# power.net
KiCad netlist of a schematic drawn in Altium Designer
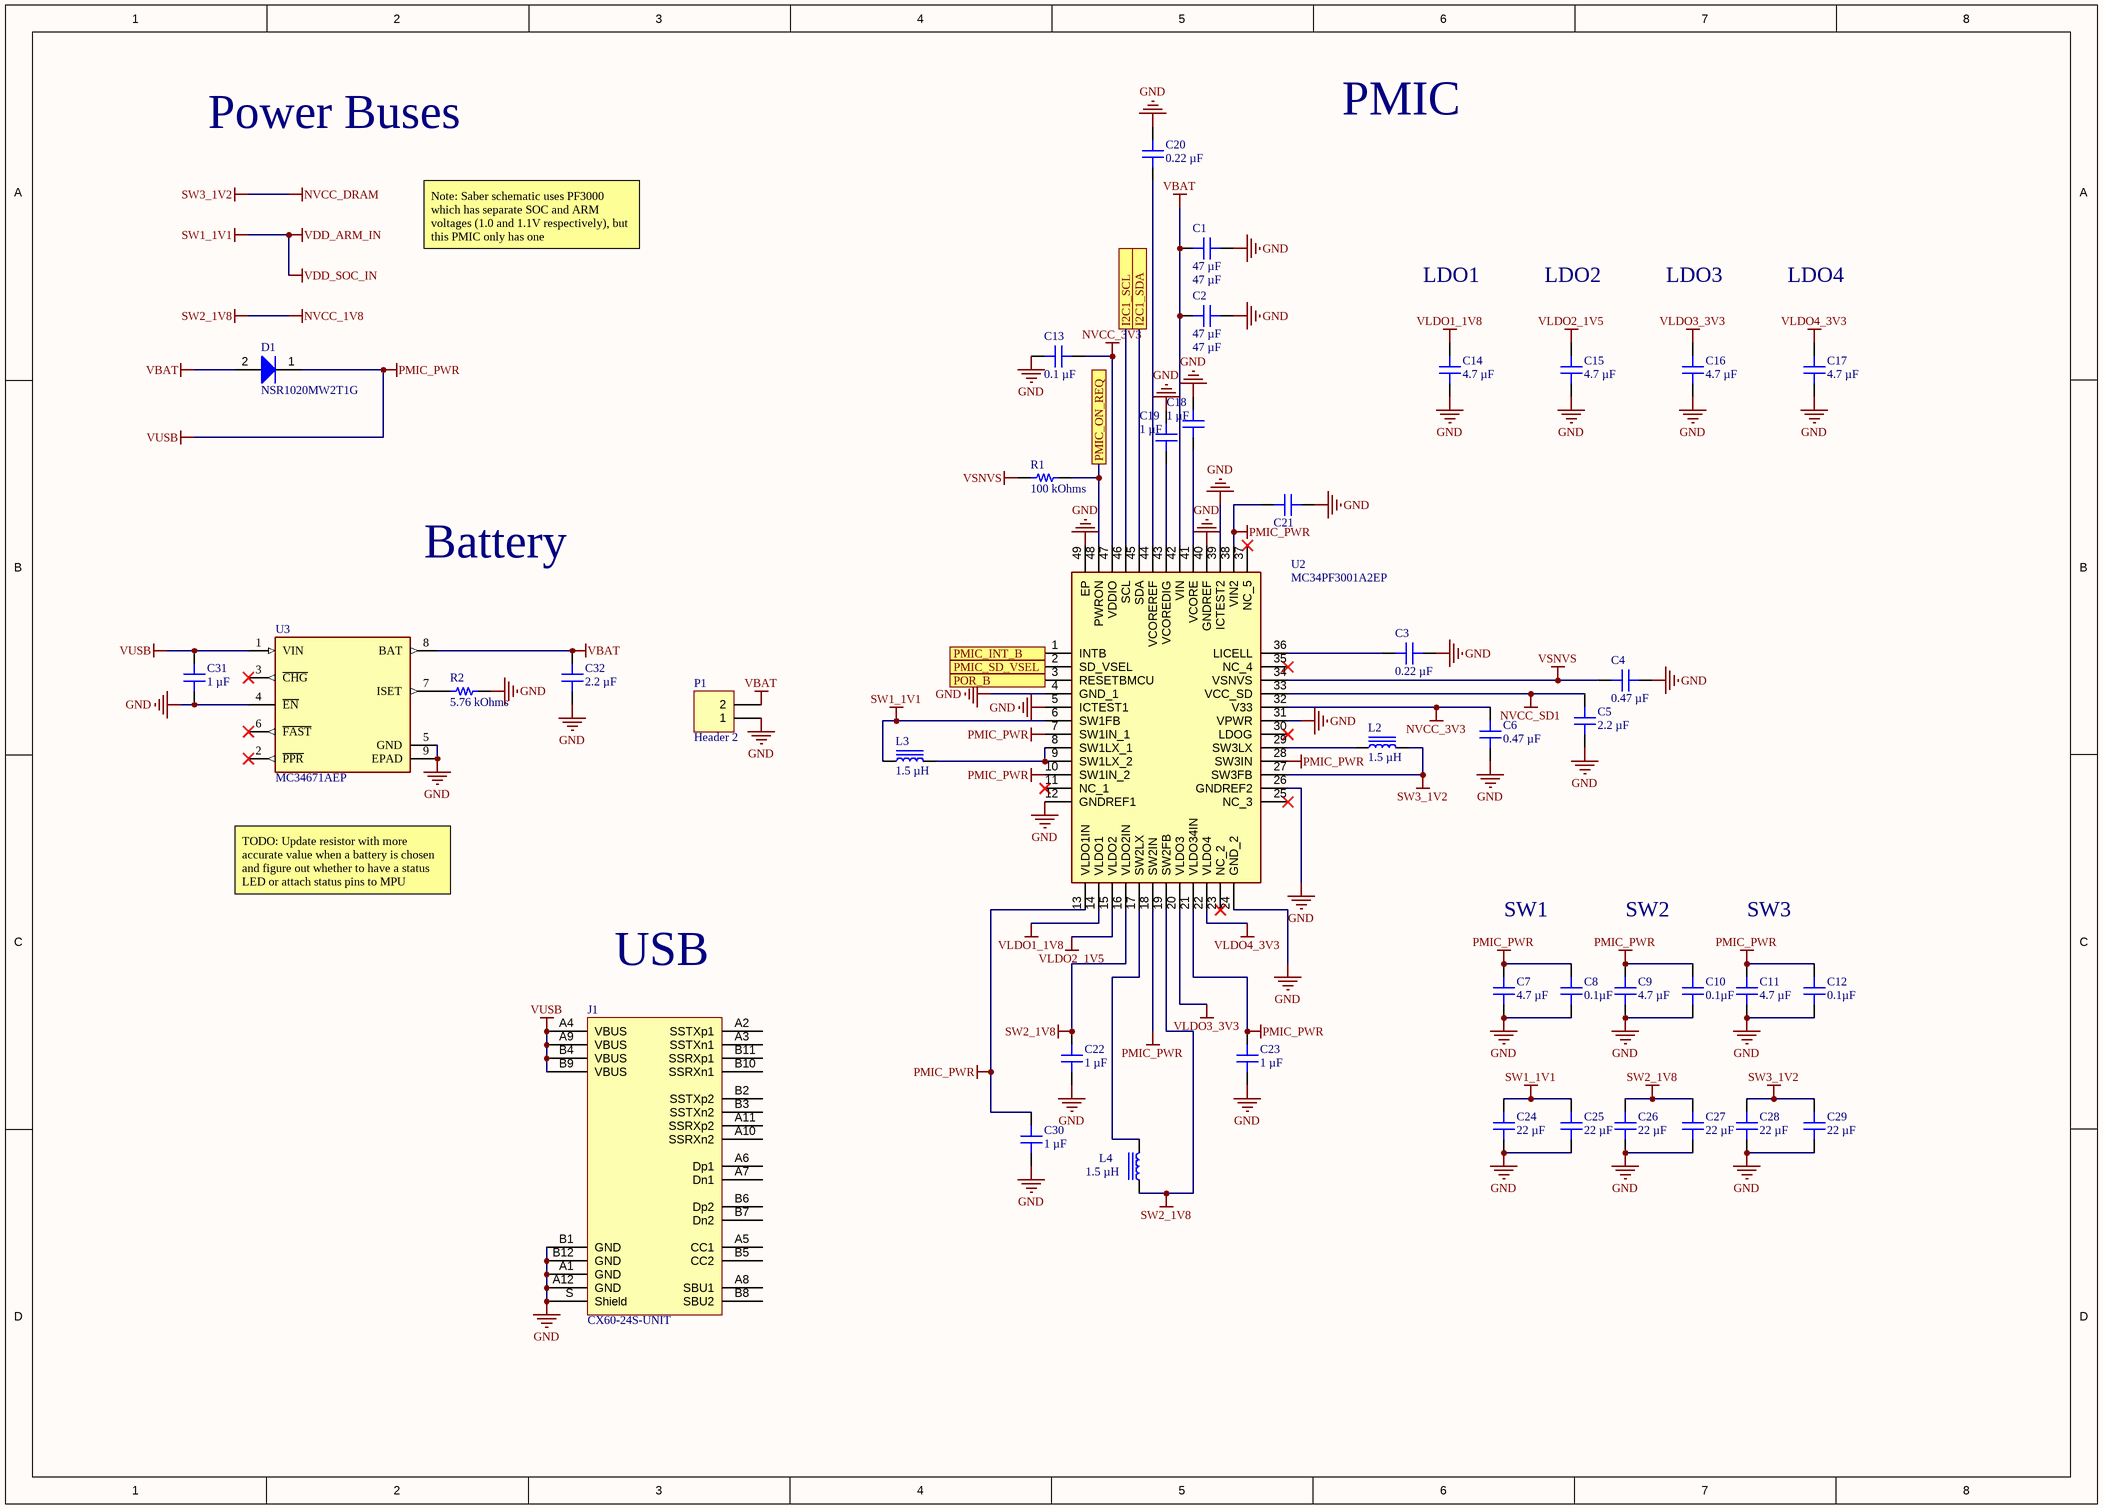
[diagram p0: power.SchDoc]

(export (version "E")
  (design (tool "Eeschema 10.0.6"))
  (components
    (comp (ref "C1")
      (value "47 µF")
      (footprint "CAP 0603_1608")
      (description "CAP CER 47UF 4V X5R 0603")
      (fields (field (name "PART NUMBER") "GRM188R60G476ME15D") (field (name "ALTIUM_VALUE") "47 µF"))
      (libsource (lib "Celestial Altium Library - altium_library") (part "Capacitor"))
    )
    (comp (ref "C2")
      (value "47 µF")
      (footprint "CAP 0603_1608")
      (description "CAP CER 47UF 4V X5R 0603")
      (fields (field (name "PART NUMBER") "GRM188R60G476ME15D") (field (name "ALTIUM_VALUE") "47 µF"))
      (libsource (lib "Celestial Altium Library - altium_library") (part "Capacitor"))
    )
    (comp (ref "C3")
      (value "0.22 µF")
      (footprint "CAP 0603_1608")
      (description "CAP CER 0.22UF 50V Y5V 0603")
      (fields (field (name "PART NUMBER") "CC0603ZRY5V9BB224") (field (name "MANUFACTURER") "Yageo"))
      (libsource (lib "Celestial Altium Library - altium_library") (part "Capacitor"))
    )
    (comp (ref "C4")
      (value "0.47 µF")
      (footprint "CAP 0603_1608")
      (description "CAP CER 0.47UF 10V X7R 0603")
      (fields
        (field (name "PART NUMBER") "CL10B474KP8NNNC")
        (field (name "MANUFACTURER") "Samsung Electro-Mechanics")
      )
      (libsource (lib "Celestial Altium Library - altium_library") (part "Capacitor"))
    )
    (comp (ref "C5")
      (value "2.2 µF")
      (footprint "CAP 0603_1608")
      (description "CAP CER 2.2UF 10V X7R 0603")
      (fields
        (field (name "PART NUMBER") "GRM188R71A225KE15D")
        (field (name "MANUFACTURER") "Murata Electronics")
      )
      (libsource (lib "Celestial Altium Library - altium_library") (part "Capacitor"))
    )
    (comp (ref "C6")
      (value "0.47 µF")
      (footprint "CAP 0603_1608")
      (description "CAP CER 0.47UF 10V X7R 0603")
      (fields
        (field (name "PART NUMBER") "CL10B474KP8NNNC")
        (field (name "MANUFACTURER") "Samsung Electro-Mechanics")
      )
      (libsource (lib "Celestial Altium Library - altium_library") (part "Capacitor"))
    )
    (comp (ref "C7")
      (value "4.7 µF")
      (footprint "CAP 0603_1608")
      (description "CAP CER 4.7UF 10V X5R 0603")
      (fields (field (name "PART NUMBER") "LMK107BJ475KAHT") (field (name "MANUFACTURER") "Taiyo Yuden"))
      (libsource (lib "Celestial Altium Library - altium_library") (part "Capacitor"))
    )
    (comp (ref "C8")
      (value "0.1µF")
      (footprint "CAP 0603_1608")
      (description "CAP CER 0.1UF 10V X7R 0603")
      (fields (field (name "PART NUMBER") "0603ZC104KAT2A") (field (name "MANUFACTURER") "AVX Corporation"))
      (libsource (lib "Celestial Altium Library - altium_library") (part "Capacitor"))
    )
    (comp (ref "C9")
      (value "4.7 µF")
      (footprint "CAP 0603_1608")
      (description "CAP CER 4.7UF 10V X5R 0603")
      (fields (field (name "PART NUMBER") "LMK107BJ475KAHT") (field (name "MANUFACTURER") "Taiyo Yuden"))
      (libsource (lib "Celestial Altium Library - altium_library") (part "Capacitor"))
    )
    (comp (ref "C10")
      (value "0.1µF")
      (footprint "CAP 0603_1608")
      (description "CAP CER 0.1UF 10V X7R 0603")
      (fields (field (name "PART NUMBER") "0603ZC104KAT2A") (field (name "MANUFACTURER") "AVX Corporation"))
      (libsource (lib "Celestial Altium Library - altium_library") (part "Capacitor"))
    )
    (comp (ref "C11")
      (value "4.7 µF")
      (footprint "CAP 0603_1608")
      (description "CAP CER 4.7UF 10V X5R 0603")
      (fields (field (name "PART NUMBER") "LMK107BJ475KAHT") (field (name "MANUFACTURER") "Taiyo Yuden"))
      (libsource (lib "Celestial Altium Library - altium_library") (part "Capacitor"))
    )
    (comp (ref "C12")
      (value "0.1µF")
      (footprint "CAP 0603_1608")
      (description "CAP CER 0.1UF 10V X7R 0603")
      (fields (field (name "PART NUMBER") "0603ZC104KAT2A") (field (name "MANUFACTURER") "AVX Corporation"))
      (libsource (lib "Celestial Altium Library - altium_library") (part "Capacitor"))
    )
    (comp (ref "C13")
      (value "0.1 µF")
      (footprint "CAP 0603_1608")
      (description "CAP CER 0.1UF 10V X7R 0603")
      (fields (field (name "PART NUMBER") "CC0603KRX7R6BB104") (field (name "MANUFACTURER") "Yageo"))
      (libsource (lib "Celestial Altium Library - altium_library") (part "Capacitor"))
    )
    (comp (ref "C14")
      (value "4.7 µF")
      (footprint "CAP 0603_1608")
      (description "CAP CER 4.7UF 10V X5R 0603")
      (fields (field (name "PART NUMBER") "LMK107BJ475KAHT") (field (name "MANUFACTURER") "Taiyo Yuden"))
      (libsource (lib "Celestial Altium Library - altium_library") (part "Capacitor"))
    )
    (comp (ref "C15")
      (value "4.7 µF")
      (footprint "CAP 0603_1608")
      (description "CAP CER 4.7UF 10V X5R 0603")
      (fields (field (name "PART NUMBER") "LMK107BJ475KAHT") (field (name "MANUFACTURER") "Taiyo Yuden"))
      (libsource (lib "Celestial Altium Library - altium_library") (part "Capacitor"))
    )
    (comp (ref "C16")
      (value "4.7 µF")
      (footprint "CAP 0603_1608")
      (description "CAP CER 4.7UF 10V X5R 0603")
      (fields (field (name "PART NUMBER") "LMK107BJ475KAHT") (field (name "MANUFACTURER") "Taiyo Yuden"))
      (libsource (lib "Celestial Altium Library - altium_library") (part "Capacitor"))
    )
    (comp (ref "C17")
      (value "4.7 µF")
      (footprint "CAP 0603_1608")
      (description "CAP CER 4.7UF 10V X5R 0603")
      (fields (field (name "PART NUMBER") "LMK107BJ475KAHT") (field (name "MANUFACTURER") "Taiyo Yuden"))
      (libsource (lib "Celestial Altium Library - altium_library") (part "Capacitor"))
    )
    (comp (ref "C18")
      (value "1 µF")
      (footprint "CAP 0603_1608")
      (description "CAP CER 0603 1UF 6.3V X7R 10%")
      (fields (field (name "PART NUMBER") "C0603C105K9RACAUTO") (field (name "MANUFACTURER") "KEMET"))
      (libsource (lib "Celestial Altium Library - altium_library") (part "Capacitor"))
    )
    (comp (ref "C19")
      (value "1 µF")
      (footprint "CAP 0603_1608")
      (description "CAP CER 0603 1UF 6.3V X7R 10%")
      (fields (field (name "PART NUMBER") "C0603C105K9RACAUTO") (field (name "MANUFACTURER") "KEMET"))
      (libsource (lib "Celestial Altium Library - altium_library") (part "Capacitor"))
    )
    (comp (ref "C20")
      (value "0.22 µF")
      (footprint "CAP 0603_1608")
      (description "CAP CER 0.22UF 50V Y5V 0603")
      (fields (field (name "PART NUMBER") "CC0603ZRY5V9BB224") (field (name "MANUFACTURER") "Yageo"))
      (libsource (lib "Celestial Altium Library - altium_library") (part "Capacitor"))
    )
    (comp (ref "C21")
      (value "CC0603KRX5R6BB106")
      (footprint "CAP 0603_1608")
      (description "CAP CER 10UF 10V X5R 0603")
      (fields (field (name "MANUFACTURER") "Yageo") (field (name "TOLERANCE") "±10%"))
      (libsource (lib "Celestial Altium Library - altium_library") (part "Capacitor"))
    )
    (comp (ref "C22")
      (value "1 µF")
      (footprint "CAP 0603_1608")
      (description "CAP CER 0603 1UF 6.3V X7R 10%")
      (fields (field (name "PART NUMBER") "C0603C105K9RACAUTO") (field (name "MANUFACTURER") "KEMET"))
      (libsource (lib "Celestial Altium Library - altium_library") (part "Capacitor"))
    )
    (comp (ref "C23")
      (value "1 µF")
      (footprint "CAP 0603_1608")
      (description "CAP CER 0603 1UF 6.3V X7R 10%")
      (fields (field (name "PART NUMBER") "C0603C105K9RACAUTO") (field (name "MANUFACTURER") "KEMET"))
      (libsource (lib "Celestial Altium Library - altium_library") (part "Capacitor"))
    )
    (comp (ref "C24")
      (value "22 µF")
      (footprint "CAP 0603_1608")
      (description "CAP CER 22UF 6.3V X5R 0603")
      (fields
        (field (name "PART NUMBER") "GRM188R60J226MEA0D")
        (field (name "MANUFACTURER") "Murata Electronics")
      )
      (libsource (lib "Celestial Altium Library - altium_library") (part "Capacitor"))
    )
    (comp (ref "C25")
      (value "22 µF")
      (footprint "CAP 0603_1608")
      (description "CAP CER 22UF 6.3V X5R 0603")
      (fields
        (field (name "PART NUMBER") "GRM188R60J226MEA0D")
        (field (name "MANUFACTURER") "Murata Electronics")
      )
      (libsource (lib "Celestial Altium Library - altium_library") (part "Capacitor"))
    )
    (comp (ref "C26")
      (value "22 µF")
      (footprint "CAP 0603_1608")
      (description "CAP CER 22UF 6.3V X5R 0603")
      (fields
        (field (name "PART NUMBER") "GRM188R60J226MEA0D")
        (field (name "MANUFACTURER") "Murata Electronics")
      )
      (libsource (lib "Celestial Altium Library - altium_library") (part "Capacitor"))
    )
    (comp (ref "C27")
      (value "22 µF")
      (footprint "CAP 0603_1608")
      (description "CAP CER 22UF 6.3V X5R 0603")
      (fields
        (field (name "PART NUMBER") "GRM188R60J226MEA0D")
        (field (name "MANUFACTURER") "Murata Electronics")
      )
      (libsource (lib "Celestial Altium Library - altium_library") (part "Capacitor"))
    )
    (comp (ref "C28")
      (value "22 µF")
      (footprint "CAP 0603_1608")
      (description "CAP CER 22UF 6.3V X5R 0603")
      (fields
        (field (name "PART NUMBER") "GRM188R60J226MEA0D")
        (field (name "MANUFACTURER") "Murata Electronics")
      )
      (libsource (lib "Celestial Altium Library - altium_library") (part "Capacitor"))
    )
    (comp (ref "C29")
      (value "22 µF")
      (footprint "CAP 0603_1608")
      (description "CAP CER 22UF 6.3V X5R 0603")
      (fields
        (field (name "PART NUMBER") "GRM188R60J226MEA0D")
        (field (name "MANUFACTURER") "Murata Electronics")
      )
      (libsource (lib "Celestial Altium Library - altium_library") (part "Capacitor"))
    )
    (comp (ref "C30")
      (value "1 µF")
      (footprint "CAP 0603_1608")
      (description "CAP CER 0603 1UF 6.3V X7R 10%")
      (fields (field (name "PART NUMBER") "C0603C105K9RACAUTO") (field (name "MANUFACTURER") "KEMET"))
      (libsource (lib "Celestial Altium Library - altium_library") (part "Capacitor"))
    )
    (comp (ref "C31")
      (value "1 µF")
      (footprint "CAP 0603_1608")
      (description "CAP CER 0603 1UF 6.3V X7R 10%")
      (fields (field (name "PART NUMBER") "C0603C105K9RACAUTO") (field (name "MANUFACTURER") "KEMET"))
      (libsource (lib "Celestial Altium Library - altium_library") (part "Capacitor"))
    )
    (comp (ref "C32")
      (value "2.2 µF")
      (footprint "CAP 0603_1608")
      (description "CAP CER 2.2UF 16V X5R 0603")
      (fields (field (name "PART NUMBER") "EMK107ABJ225KAHT") (field (name "MANUFACTURER") "Taiyo Yuden"))
      (libsource (lib "Celestial Altium Library - altium_library") (part "Capacitor"))
    )
    (comp (ref "D1")
      (value "NSR1020MW2T1G")
      (footprint "ONSC-SOD-323-2-477-02_V")
      (description "Schottky Barrier Diode, 2-Pin SOD-323, Pb-Free, Tape and Reel")
      (fields (field (name "MANUFACTURER") "On Semiconductor"))
      (libsource (lib "Altium Content Vault") (part "ONSC-D-K1A2-2"))
    )
    (comp (ref "J1")
      (value "CX60-24S-UNIT")
      (footprint "HIROSE CX60-24S-UNIT")
      (description "CONN USB 3.1 TYPE C PLUG UNIT")
      (fields (field (name "MANUFACTURER") "Hirose Electric Co Ltd"))
      (libsource (lib "Celestial Altium Library - altium_library") (part "USB 3.0 Type C"))
    )
    (comp (ref "L2")
      (value "1.5 µH")
      (footprint "IND 0806_2016")
      (description "FIXED IND 1.5UH 2.4A 99MOHM SMD")
      (fields
        (field (name "PART NUMBER") "MPI2010V1-1R5-R")
        (field (name "MANUFACTURER") "Eaton - Electronics Division")
      )
      (libsource (lib "Celestial Altium Library - altium_library") (part "Inductor"))
    )
    (comp (ref "L3")
      (value "1.5 µH")
      (footprint "IND 0806_2016")
      (description "FIXED IND 1.5UH 2.4A 99MOHM SMD")
      (fields
        (field (name "PART NUMBER") "MPI2010V1-1R5-R")
        (field (name "MANUFACTURER") "Eaton - Electronics Division")
      )
      (libsource (lib "Celestial Altium Library - altium_library") (part "Inductor"))
    )
    (comp (ref "L4")
      (value "1.5 µH")
      (footprint "IND 0806_2016")
      (description "FIXED IND 1.5UH 2.4A 99MOHM SMD")
      (fields
        (field (name "PART NUMBER") "MPI2010V1-1R5-R")
        (field (name "MANUFACTURER") "Eaton - Electronics Division")
      )
      (libsource (lib "Celestial Altium Library - altium_library") (part "Inductor"))
    )
    (comp (ref "P1")
      (value "Header 2")
      (footprint "HDR1X2")
      (description "Header, 2-Pin")
      (fields (field (name "PUBLISHER") "Altium Limited"))
      (libsource (lib "Miscellaneous Connectors") (part "Header 2"))
    )
    (comp (ref "R1")
      (value "100 kOhms")
      (footprint "RES 0603_1608")
      (description "RES SMD 100K OHM 5% 1/10W 0603")
      (fields
        (field (name "PART NUMBER") "ERJ-3GEYJ104V")
        (field (name "MANUFACTURER") "Panasonic Electronic Components")
      )
      (libsource (lib "Celestial Altium Library - altium_library") (part "Resistor"))
    )
    (comp (ref "R2")
      (value "5.76 kOhms")
      (footprint "RES 0603_1608")
      (description "RES SMD 5.76KOHM 0.5% 1/16W 0603")
      (fields (field (name "PART NUMBER") "RR0816P-5761-D-74H") (field (name "MANUFACTURER") "Susumu"))
      (libsource (lib "Celestial Altium Library - altium_library") (part "Resistor"))
    )
    (comp (ref "U2")
      (value "MC34PF3001A2EP")
      (footprint "SamacSys:QFN50P700X700X90-49N-D")
      (description "Integrated Circuit")
      (fields
        (field (name "MANUFACTURER_PART_NUMBER") "MC34PF3001A3EP")
        (field (name "MOUSER PART NUMBER") "841-MC34PF3001A3EP")
      )
      (libsource (lib "*") (part "MC34PF3001A3EP"))
    )
    (comp (ref "U3")
      (value "MC34671AEP")
      (footprint "FP-SOT1590-2-IPC_C")
      (description "IC BATT CHG LI-ION 1CELL 8UDFN")
      (libsource (lib "Altium Content Vault") (part "9e0dd3b147da4dca80ccce6c448a326"))
    )
  )
  (nets
    (net (code "1") (name "/I2C1_SCL") (class "Default")
      (node (ref "U2") (pin "46") (pinfunction "SCL_46") (pintype "passive"))
    )
    (net (code "2") (name "/I2C1_SDA") (class "Default")
      (node (ref "U2") (pin "45") (pinfunction "SDA_45") (pintype "passive"))
    )
    (net (code "3") (name "/PMIC_INT_B") (class "Default")
      (node (ref "U2") (pin "1") (pinfunction "INTB_1") (pintype "passive"))
    )
    (net (code "4") (name "/PMIC_ON_REQ") (class "Default")
      (node (ref "R1") (pin "2") (pinfunction "2_2") (pintype "passive"))
      (node (ref "U2") (pin "48") (pinfunction "PWRON_48") (pintype "passive"))
    )
    (net (code "5") (name "/PMIC_SD_VSEL") (class "Default")
      (node (ref "U2") (pin "2") (pinfunction "SD_VSEL_2") (pintype "passive"))
    )
    (net (code "6") (name "/POR_B") (class "Default")
      (node (ref "U2") (pin "3") (pinfunction "RESETBMCU_3") (pintype "passive"))
    )
    (net (code "7") (name "GND") (class "Default")
      (node (ref "C1") (pin "2") (pinfunction "2_2") (pintype "passive"))
      (node (ref "C10") (pin "1") (pinfunction "1_1") (pintype "passive"))
      (node (ref "C11") (pin "1") (pinfunction "1_1") (pintype "passive"))
      (node (ref "C12") (pin "1") (pinfunction "1_1") (pintype "passive"))
      (node (ref "C13") (pin "1") (pinfunction "1_1") (pintype "passive"))
      (node (ref "C14") (pin "1") (pinfunction "1_1") (pintype "passive"))
      (node (ref "C15") (pin "1") (pinfunction "1_1") (pintype "passive"))
      (node (ref "C16") (pin "1") (pinfunction "1_1") (pintype "passive"))
      (node (ref "C17") (pin "1") (pinfunction "1_1") (pintype "passive"))
      (node (ref "C18") (pin "2") (pinfunction "2_2") (pintype "passive"))
      (node (ref "C19") (pin "2") (pinfunction "2_2") (pintype "passive"))
      (node (ref "C2") (pin "2") (pinfunction "2_2") (pintype "passive"))
      (node (ref "C20") (pin "2") (pinfunction "2_2") (pintype "passive"))
      (node (ref "C21") (pin "2") (pinfunction "2_2") (pintype "passive"))
      (node (ref "C22") (pin "1") (pinfunction "1_1") (pintype "passive"))
      (node (ref "C23") (pin "1") (pinfunction "1_1") (pintype "passive"))
      (node (ref "C24") (pin "2") (pinfunction "2_2") (pintype "passive"))
      (node (ref "C25") (pin "2") (pinfunction "2_2") (pintype "passive"))
      (node (ref "C26") (pin "2") (pinfunction "2_2") (pintype "passive"))
      (node (ref "C27") (pin "2") (pinfunction "2_2") (pintype "passive"))
      (node (ref "C28") (pin "2") (pinfunction "2_2") (pintype "passive"))
      (node (ref "C29") (pin "2") (pinfunction "2_2") (pintype "passive"))
      (node (ref "C3") (pin "2") (pinfunction "2_2") (pintype "passive"))
      (node (ref "C30") (pin "1") (pinfunction "1_1") (pintype "passive"))
      (node (ref "C31") (pin "1") (pinfunction "1_1") (pintype "passive"))
      (node (ref "C32") (pin "1") (pinfunction "1_1") (pintype "passive"))
      (node (ref "C4") (pin "2") (pinfunction "2_2") (pintype "passive"))
      (node (ref "C5") (pin "1") (pinfunction "1_1") (pintype "passive"))
      (node (ref "C6") (pin "2") (pinfunction "2_2") (pintype "passive"))
      (node (ref "C7") (pin "1") (pinfunction "1_1") (pintype "passive"))
      (node (ref "C8") (pin "1") (pinfunction "1_1") (pintype "passive"))
      (node (ref "C9") (pin "1") (pinfunction "1_1") (pintype "passive"))
      (node (ref "J1") (pin "A1") (pinfunction "GND_A1") (pintype "passive"))
      (node (ref "J1") (pin "A12") (pinfunction "GND_A12") (pintype "passive"))
      (node (ref "J1") (pin "B1") (pinfunction "GND_B1") (pintype "passive"))
      (node (ref "J1") (pin "B12") (pinfunction "GND_B12") (pintype "passive"))
      (node (ref "J1") (pin "S") (pinfunction "Shield_S") (pintype "passive"))
      (node (ref "P1") (pin "1") (pinfunction "1_1") (pintype "passive"))
      (node (ref "R2") (pin "2") (pinfunction "2_2") (pintype "passive"))
      (node (ref "U2") (pin "12") (pinfunction "GNDREF1_12") (pintype "passive"))
      (node (ref "U2") (pin "24") (pinfunction "GND_2_24") (pintype "passive"))
      (node (ref "U2") (pin "26") (pinfunction "GNDREF2_26") (pintype "passive"))
      (node (ref "U2") (pin "31") (pinfunction "VPWR_31") (pintype "passive"))
      (node (ref "U2") (pin "39") (pinfunction "ICTEST2_39") (pintype "passive"))
      (node (ref "U2") (pin "4") (pinfunction "GND_1_4") (pintype "passive"))
      (node (ref "U2") (pin "40") (pinfunction "GNDREF_40") (pintype "passive"))
      (node (ref "U2") (pin "49") (pinfunction "EP_49") (pintype "passive"))
      (node (ref "U2") (pin "5") (pinfunction "ICTEST1_5") (pintype "passive"))
      (node (ref "U3") (pin "4") (pinfunction "~{EN}_4") (pintype "passive"))
      (node (ref "U3") (pin "5") (pinfunction "GND_5") (pintype "power_in"))
      (node (ref "U3") (pin "9") (pinfunction "EPAD_9") (pintype "passive"))
    )
    (net (code "8") (name "NVCC_1V8") (class "Default")
      (node (ref "C22") (pin "2") (pinfunction "2_2") (pintype "passive"))
      (node (ref "C26") (pin "1") (pinfunction "1_1") (pintype "passive"))
      (node (ref "C27") (pin "1") (pinfunction "1_1") (pintype "passive"))
      (node (ref "L4") (pin "1") (pinfunction "1_1") (pintype "passive"))
      (node (ref "U2") (pin "16") (pinfunction "VLDO2IN_16") (pintype "passive"))
      (node (ref "U2") (pin "19") (pinfunction "SW2FB_19") (pintype "passive"))
    )
    (net (code "9") (name "NVCC_3V3") (class "Default")
      (node (ref "C13") (pin "2") (pinfunction "2_2") (pintype "passive"))
      (node (ref "C6") (pin "1") (pinfunction "1_1") (pintype "passive"))
      (node (ref "U2") (pin "32") (pinfunction "V33_32") (pintype "passive"))
      (node (ref "U2") (pin "47") (pinfunction "VDDIO_47") (pintype "passive"))
    )
    (net (code "10") (name "NVCC_DRAM") (class "Default")
      (node (ref "C28") (pin "1") (pinfunction "1_1") (pintype "passive"))
      (node (ref "C29") (pin "1") (pinfunction "1_1") (pintype "passive"))
      (node (ref "L2") (pin "2") (pinfunction "2_2") (pintype "passive"))
      (node (ref "U2") (pin "27") (pinfunction "SW3FB_27") (pintype "passive"))
    )
    (net (code "11") (name "NVCC_SD1") (class "Default")
      (node (ref "C5") (pin "2") (pinfunction "2_2") (pintype "passive"))
      (node (ref "U2") (pin "33") (pinfunction "VCC_SD_33") (pintype "passive"))
    )
    (net (code "12") (name "Net-(U2-LICELL)") (class "Default")
      (node (ref "C3") (pin "1") (pinfunction "1_1") (pintype "passive"))
      (node (ref "U2") (pin "36") (pinfunction "LICELL_36") (pintype "passive"))
    )
    (net (code "13") (name "Net-(U2-SW1LX_1)") (class "Default")
      (node (ref "L3") (pin "2") (pinfunction "2_2") (pintype "passive"))
      (node (ref "U2") (pin "8") (pinfunction "SW1LX_1_8") (pintype "passive"))
      (node (ref "U2") (pin "9") (pinfunction "SW1LX_2_9") (pintype "passive"))
    )
    (net (code "14") (name "Net-(U2-SW2LX)") (class "Default")
      (node (ref "L4") (pin "2") (pinfunction "2_2") (pintype "passive"))
      (node (ref "U2") (pin "17") (pinfunction "SW2LX_17") (pintype "passive"))
    )
    (net (code "15") (name "Net-(U2-SW3LX)") (class "Default")
      (node (ref "L2") (pin "1") (pinfunction "1_1") (pintype "passive"))
      (node (ref "U2") (pin "29") (pinfunction "SW3LX_29") (pintype "passive"))
    )
    (net (code "16") (name "Net-(U2-VCORE)") (class "Default")
      (node (ref "C18") (pin "1") (pinfunction "1_1") (pintype "passive"))
      (node (ref "U2") (pin "41") (pinfunction "VCORE_41") (pintype "passive"))
    )
    (net (code "17") (name "Net-(U2-VCOREDIG)") (class "Default")
      (node (ref "C19") (pin "1") (pinfunction "1_1") (pintype "passive"))
      (node (ref "U2") (pin "43") (pinfunction "VCOREDIG_43") (pintype "passive"))
    )
    (net (code "18") (name "Net-(U2-VCOREREF)") (class "Default")
      (node (ref "C20") (pin "1") (pinfunction "1_1") (pintype "passive"))
      (node (ref "U2") (pin "44") (pinfunction "VCOREREF_44") (pintype "passive"))
    )
    (net (code "19") (name "Net-(U3-ISET)") (class "Default")
      (node (ref "R2") (pin "1") (pinfunction "1_1") (pintype "passive"))
      (node (ref "U3") (pin "7") (pinfunction "ISET_7") (pintype "output"))
    )
    (net (code "20") (name "PMIC_PWR") (class "Default")
      (node (ref "C10") (pin "2") (pinfunction "2_2") (pintype "passive"))
      (node (ref "C11") (pin "2") (pinfunction "2_2") (pintype "passive"))
      (node (ref "C12") (pin "2") (pinfunction "2_2") (pintype "passive"))
      (node (ref "C21") (pin "1") (pinfunction "1_1") (pintype "passive"))
      (node (ref "C23") (pin "2") (pinfunction "2_2") (pintype "passive"))
      (node (ref "C30") (pin "2") (pinfunction "2_2") (pintype "passive"))
      (node (ref "C31") (pin "2") (pinfunction "2_2") (pintype "passive"))
      (node (ref "C7") (pin "2") (pinfunction "2_2") (pintype "passive"))
      (node (ref "C8") (pin "2") (pinfunction "2_2") (pintype "passive"))
      (node (ref "C9") (pin "2") (pinfunction "2_2") (pintype "passive"))
      (node (ref "D1") (pin "1") (pinfunction "K_1") (pintype "passive"))
      (node (ref "J1") (pin "A4") (pinfunction "VBUS_A4") (pintype "passive"))
      (node (ref "J1") (pin "A9") (pinfunction "VBUS_A9") (pintype "passive"))
      (node (ref "J1") (pin "B4") (pinfunction "VBUS_B4") (pintype "passive"))
      (node (ref "J1") (pin "B9") (pinfunction "VBUS_B9") (pintype "passive"))
      (node (ref "U2") (pin "10") (pinfunction "SW1IN_2_10") (pintype "passive"))
      (node (ref "U2") (pin "13") (pinfunction "VLDO1IN_13") (pintype "passive"))
      (node (ref "U2") (pin "18") (pinfunction "SW2IN_18") (pintype "passive"))
      (node (ref "U2") (pin "21") (pinfunction "VLDO34IN_21") (pintype "passive"))
      (node (ref "U2") (pin "28") (pinfunction "SW3IN_28") (pintype "passive"))
      (node (ref "U2") (pin "38") (pinfunction "VIN2_38") (pintype "passive"))
      (node (ref "U2") (pin "7") (pinfunction "SW1IN_1_7") (pintype "passive"))
      (node (ref "U3") (pin "1") (pinfunction "VIN_1") (pintype "input"))
    )
    (net (code "21") (name "SW1_1V1") (class "Default")
      (node (ref "C24") (pin "1") (pinfunction "1_1") (pintype "passive"))
      (node (ref "C25") (pin "1") (pinfunction "1_1") (pintype "passive"))
      (node (ref "L3") (pin "1") (pinfunction "1_1") (pintype "passive"))
      (node (ref "U2") (pin "6") (pinfunction "SW1FB_6") (pintype "passive"))
    )
    (net (code "22") (name "VBAT") (class "Default")
      (node (ref "C1") (pin "1") (pinfunction "1_1") (pintype "passive"))
      (node (ref "C2") (pin "1") (pinfunction "1_1") (pintype "passive"))
      (node (ref "C32") (pin "2") (pinfunction "2_2") (pintype "passive"))
      (node (ref "D1") (pin "2") (pinfunction "A_2") (pintype "passive"))
      (node (ref "P1") (pin "2") (pinfunction "2_2") (pintype "passive"))
      (node (ref "U2") (pin "42") (pinfunction "VIN_42") (pintype "passive"))
      (node (ref "U3") (pin "8") (pinfunction "BAT_8") (pintype "output"))
    )
    (net (code "23") (name "VLDO1_1V8") (class "Default")
      (node (ref "C14") (pin "2") (pinfunction "2_2") (pintype "passive"))
      (node (ref "U2") (pin "14") (pinfunction "VLDO1_14") (pintype "passive"))
    )
    (net (code "24") (name "VLDO2_1V5") (class "Default")
      (node (ref "C15") (pin "2") (pinfunction "2_2") (pintype "passive"))
      (node (ref "U2") (pin "15") (pinfunction "VLDO2_15") (pintype "passive"))
    )
    (net (code "25") (name "VLDO3_3V3") (class "Default")
      (node (ref "C16") (pin "2") (pinfunction "2_2") (pintype "passive"))
      (node (ref "U2") (pin "20") (pinfunction "VLDO3_20") (pintype "passive"))
    )
    (net (code "26") (name "VLDO4_3V3") (class "Default")
      (node (ref "C17") (pin "2") (pinfunction "2_2") (pintype "passive"))
      (node (ref "U2") (pin "22") (pinfunction "VLDO4_22") (pintype "passive"))
    )
    (net (code "27") (name "VSNVS") (class "Default")
      (node (ref "C4") (pin "1") (pinfunction "1_1") (pintype "passive"))
      (node (ref "R1") (pin "1") (pinfunction "1_1") (pintype "passive"))
      (node (ref "U2") (pin "34") (pinfunction "VSNVS_34") (pintype "passive"))
    )
    (net (code "28") (name "unconnected-(J1-CC1-PadA5)") (class "Default")
      (node (ref "J1") (pin "A5") (pinfunction "CC1_A5") (pintype "passive"))
    )
    (net (code "29") (name "unconnected-(J1-CC2-PadB5)") (class "Default")
      (node (ref "J1") (pin "B5") (pinfunction "CC2_B5") (pintype "passive"))
    )
    (net (code "30") (name "unconnected-(J1-Dn1-PadA7)") (class "Default")
      (node (ref "J1") (pin "A7") (pinfunction "Dn1_A7") (pintype "passive"))
    )
    (net (code "31") (name "unconnected-(J1-Dn2-PadB7)") (class "Default")
      (node (ref "J1") (pin "B7") (pinfunction "Dn2_B7") (pintype "passive"))
    )
    (net (code "32") (name "unconnected-(J1-Dp1-PadA6)") (class "Default")
      (node (ref "J1") (pin "A6") (pinfunction "Dp1_A6") (pintype "passive"))
    )
    (net (code "33") (name "unconnected-(J1-Dp2-PadB6)") (class "Default")
      (node (ref "J1") (pin "B6") (pinfunction "Dp2_B6") (pintype "passive"))
    )
    (net (code "34") (name "unconnected-(J1-SBU1-PadA8)") (class "Default")
      (node (ref "J1") (pin "A8") (pinfunction "SBU1_A8") (pintype "passive"))
    )
    (net (code "35") (name "unconnected-(J1-SBU2-PadB8)") (class "Default")
      (node (ref "J1") (pin "B8") (pinfunction "SBU2_B8") (pintype "passive"))
    )
    (net (code "36") (name "unconnected-(J1-SSRXn1-PadB10)") (class "Default")
      (node (ref "J1") (pin "B10") (pinfunction "SSRXn1_B10") (pintype "passive"))
    )
    (net (code "37") (name "unconnected-(J1-SSRXn2-PadA10)") (class "Default")
      (node (ref "J1") (pin "A10") (pinfunction "SSRXn2_A10") (pintype "passive"))
    )
    (net (code "38") (name "unconnected-(J1-SSRXp1-PadB11)") (class "Default")
      (node (ref "J1") (pin "B11") (pinfunction "SSRXp1_B11") (pintype "passive"))
    )
    (net (code "39") (name "unconnected-(J1-SSRXp2-PadA11)") (class "Default")
      (node (ref "J1") (pin "A11") (pinfunction "SSRXp2_A11") (pintype "passive"))
    )
    (net (code "40") (name "unconnected-(J1-SSTXn1-PadA3)") (class "Default")
      (node (ref "J1") (pin "A3") (pinfunction "SSTXn1_A3") (pintype "passive"))
    )
    (net (code "41") (name "unconnected-(J1-SSTXn2-PadB3)") (class "Default")
      (node (ref "J1") (pin "B3") (pinfunction "SSTXn2_B3") (pintype "passive"))
    )
    (net (code "42") (name "unconnected-(J1-SSTXp1-PadA2)") (class "Default")
      (node (ref "J1") (pin "A2") (pinfunction "SSTXp1_A2") (pintype "passive"))
    )
    (net (code "43") (name "unconnected-(J1-SSTXp2-PadB2)") (class "Default")
      (node (ref "J1") (pin "B2") (pinfunction "SSTXp2_B2") (pintype "passive"))
    )
    (net (code "44") (name "unconnected-(U2-LDOG-Pad30)") (class "Default")
      (node (ref "U2") (pin "30") (pinfunction "LDOG_30") (pintype "passive+no_connect"))
    )
    (net (code "45") (name "unconnected-(U2-NC_1-Pad11)") (class "Default")
      (node (ref "U2") (pin "11") (pinfunction "NC_1_11") (pintype "passive+no_connect"))
    )
    (net (code "46") (name "unconnected-(U2-NC_2-Pad23)") (class "Default")
      (node (ref "U2") (pin "23") (pinfunction "NC_2_23") (pintype "passive+no_connect"))
    )
    (net (code "47") (name "unconnected-(U2-NC_3-Pad25)") (class "Default")
      (node (ref "U2") (pin "25") (pinfunction "NC_3_25") (pintype "passive+no_connect"))
    )
    (net (code "48") (name "unconnected-(U2-NC_4-Pad35)") (class "Default")
      (node (ref "U2") (pin "35") (pinfunction "NC_4_35") (pintype "passive+no_connect"))
    )
    (net (code "49") (name "unconnected-(U2-NC_5-Pad37)") (class "Default")
      (node (ref "U2") (pin "37") (pinfunction "NC_5_37") (pintype "passive+no_connect"))
    )
    (net (code "50") (name "unconnected-(U3-~{CHG}-Pad3)") (class "Default")
      (node (ref "U3") (pin "3") (pinfunction "~{CHG}_3") (pintype "output+no_connect"))
    )
    (net (code "51") (name "unconnected-(U3-~{FAST}-Pad6)") (class "Default")
      (node (ref "U3") (pin "6") (pinfunction "~{FAST}_6") (pintype "output+no_connect"))
    )
    (net (code "52") (name "unconnected-(U3-~{PPR}-Pad2)") (class "Default")
      (node (ref "U3") (pin "2") (pinfunction "~{PPR}_2") (pintype "output+no_connect"))
    )
  )
)
